# SpeakModule.net
KiCad netlist of a schematic drawn in EAGLE
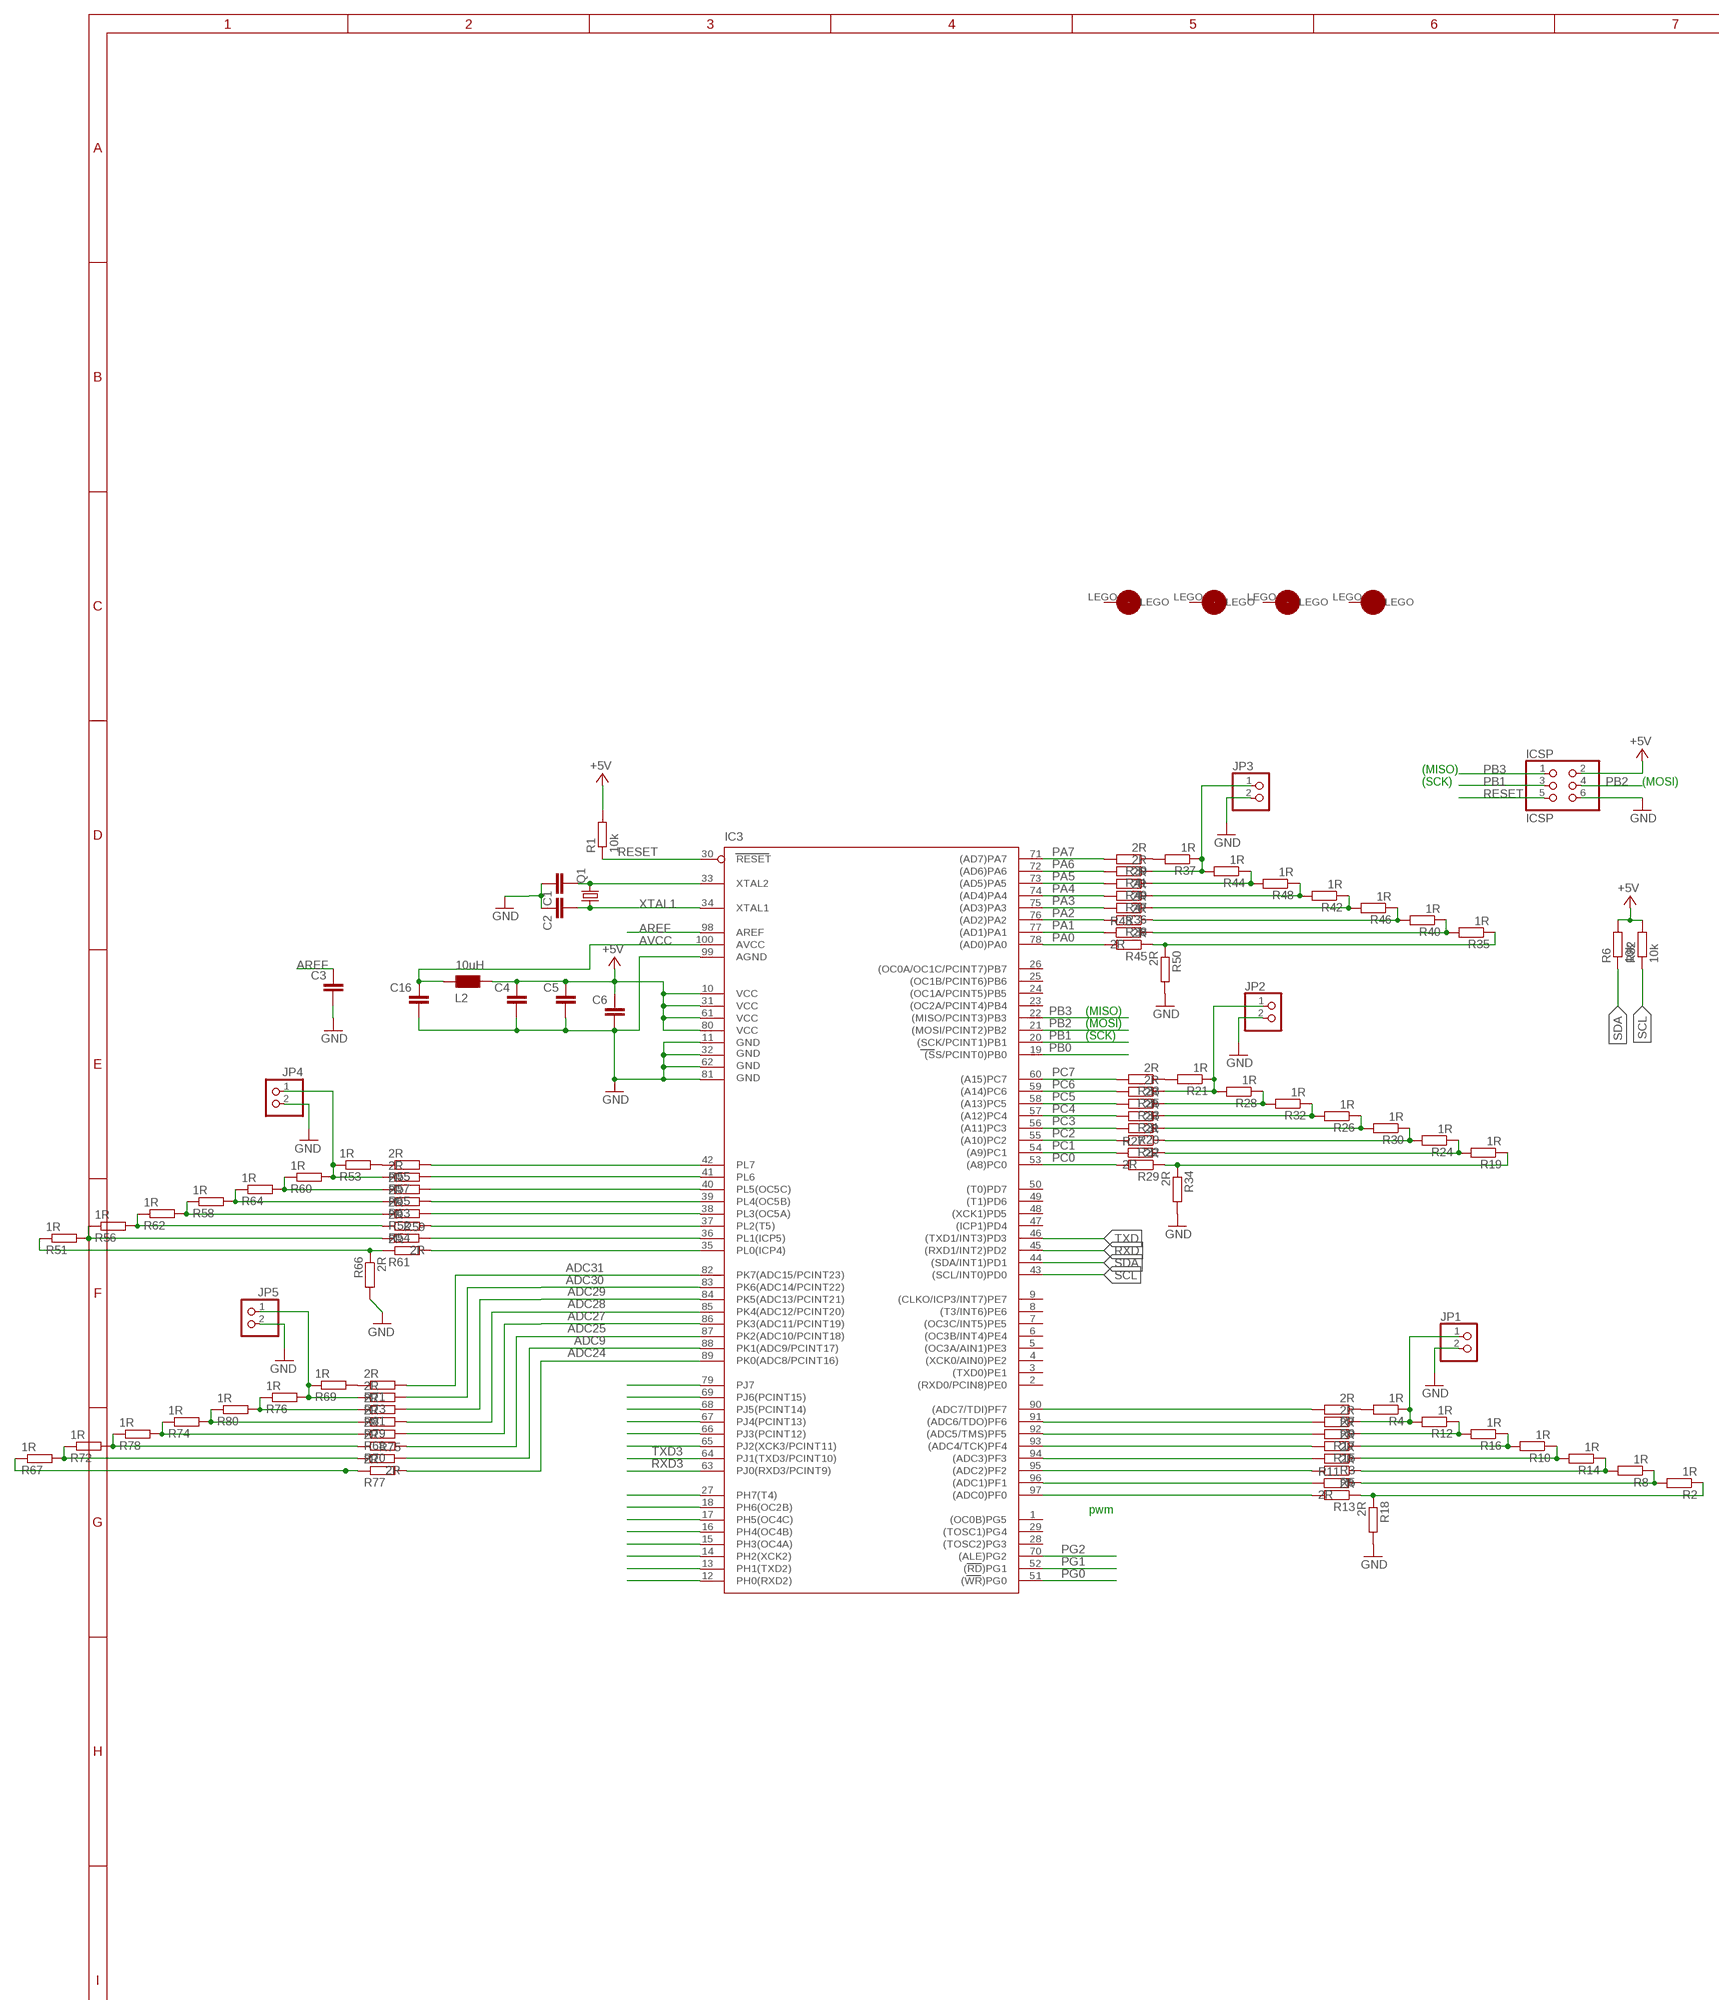
[diagram p0: schematic, sheet 1, part 1 of 2]
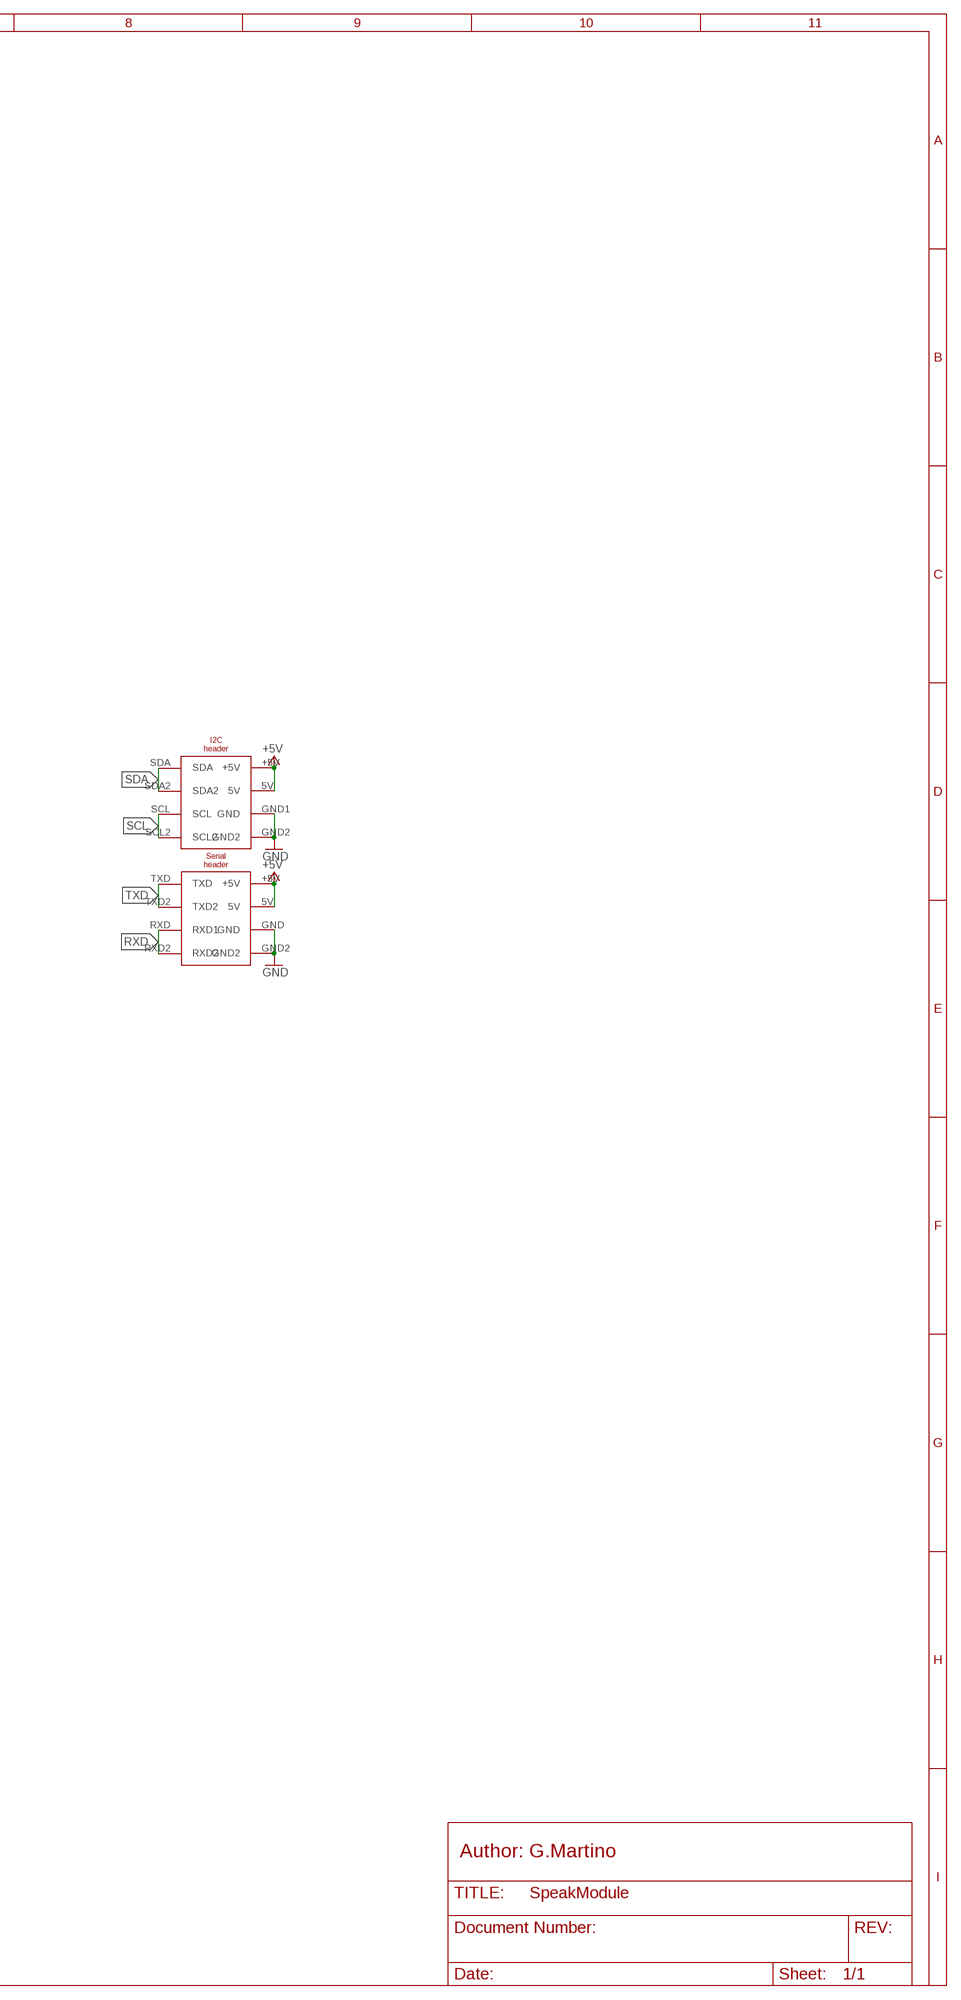
[diagram p1: schematic, sheet 1, part 2 of 2]

(export (version "E")
  (design (tool "Eeschema 10.0.6"))
  (components
    (comp (ref "C1")
      (value "22pf")
      (footprint "eagle-import:C1206")
      (libsource (lib "eagle-import") (part "C-EUC1206"))
    )
    (comp (ref "C2")
      (value "22pf")
      (footprint "eagle-import:C1206")
      (libsource (lib "eagle-import") (part "C-EUC1206"))
    )
    (comp (ref "C3")
      (value "100nF")
      (footprint "eagle-import:C1206")
      (libsource (lib "eagle-import") (part "C-EUC1206"))
    )
    (comp (ref "C4")
      (value "100nF")
      (footprint "eagle-import:C1206")
      (libsource (lib "eagle-import") (part "C-EUC1206"))
    )
    (comp (ref "C5")
      (value "100nF")
      (footprint "eagle-import:C1206")
      (libsource (lib "eagle-import") (part "C-EUC1206"))
    )
    (comp (ref "C6")
      (value "100nF")
      (footprint "eagle-import:C1206")
      (libsource (lib "eagle-import") (part "C-EUC1206"))
    )
    (comp (ref "C16")
      (value "100nF")
      (footprint "eagle-import:C1206")
      (libsource (lib "eagle-import") (part "C-EUC1206"))
    )
    (comp (ref "IC3")
      (value "ATMEGA2560-15AU")
      (footprint "eagle-import:TQFP100")
      (fields (field (name "PART_NUMBER") "ATMEGA2560-16AU"))
      (libsource (lib "eagle-import") (part "0023_ATMEGA2560-16AU"))
    )
    (comp (ref "ICSP")
      (value "ICSP")
      (footprint "eagle-import:2X03")
      (fields (field (name "PART_NUMBER") "PH254-203DF118A00V"))
      (libsource (lib "eagle-import") (part "0114_PH254-203DF118A00V"))
    )
    (comp (ref "JP1")
      (value "PINHD-1X2")
      (footprint "eagle-import:1X02")
      (libsource (lib "eagle-import") (part "PINHD-1X2"))
    )
    (comp (ref "JP2")
      (value "PINHD-1X2")
      (footprint "eagle-import:1X02")
      (libsource (lib "eagle-import") (part "PINHD-1X2"))
    )
    (comp (ref "JP3")
      (value "PINHD-1X2")
      (footprint "eagle-import:1X02")
      (libsource (lib "eagle-import") (part "PINHD-1X2"))
    )
    (comp (ref "JP4")
      (value "PINHD-1X2")
      (footprint "eagle-import:1X02")
      (libsource (lib "eagle-import") (part "PINHD-1X2"))
    )
    (comp (ref "JP5")
      (value "PINHD-1X2")
      (footprint "eagle-import:1X02")
      (libsource (lib "eagle-import") (part "PINHD-1X2"))
    )
    (comp (ref "L2")
      (value "10uH")
      (footprint "eagle-import:0805")
      (fields (field (name "PART_NUMBER") "CV201210-100K"))
      (libsource (lib "eagle-import") (part "0715_CV201210-100K"))
    )
    (comp (ref "Q1")
      (value "CRYSTALHC49S")
      (footprint "eagle-import:HC49_S")
      (libsource (lib "eagle-import") (part "CRYSTALHC49S"))
    )
    (comp (ref "R1")
      (value "10k")
      (footprint "eagle-import:M1206")
      (libsource (lib "eagle-import") (part "R-EU_M1206"))
    )
    (comp (ref "R2")
      (value "1R")
      (footprint "eagle-import:M1206")
      (libsource (lib "eagle-import") (part "R-EU_M1206"))
    )
    (comp (ref "R3")
      (value "2R")
      (footprint "eagle-import:M1206")
      (libsource (lib "eagle-import") (part "R-EU_M1206"))
    )
    (comp (ref "R4")
      (value "1R")
      (footprint "eagle-import:M1206")
      (libsource (lib "eagle-import") (part "R-EU_M1206"))
    )
    (comp (ref "R5")
      (value "2R")
      (footprint "eagle-import:M1206")
      (libsource (lib "eagle-import") (part "R-EU_M1206"))
    )
    (comp (ref "R6")
      (value "10k")
      (footprint "eagle-import:M1206")
      (libsource (lib "eagle-import") (part "R-EU_M1206"))
    )
    (comp (ref "R7")
      (value "2R")
      (footprint "eagle-import:M1206")
      (libsource (lib "eagle-import") (part "R-EU_M1206"))
    )
    (comp (ref "R8")
      (value "1R")
      (footprint "eagle-import:M1206")
      (libsource (lib "eagle-import") (part "R-EU_M1206"))
    )
    (comp (ref "R9")
      (value "2R")
      (footprint "eagle-import:M1206")
      (libsource (lib "eagle-import") (part "R-EU_M1206"))
    )
    (comp (ref "R10")
      (value "1R")
      (footprint "eagle-import:M1206")
      (libsource (lib "eagle-import") (part "R-EU_M1206"))
    )
    (comp (ref "R11")
      (value "2R")
      (footprint "eagle-import:M1206")
      (libsource (lib "eagle-import") (part "R-EU_M1206"))
    )
    (comp (ref "R12")
      (value "1R")
      (footprint "eagle-import:M1206")
      (libsource (lib "eagle-import") (part "R-EU_M1206"))
    )
    (comp (ref "R13")
      (value "2R")
      (footprint "eagle-import:M1206")
      (libsource (lib "eagle-import") (part "R-EU_M1206"))
    )
    (comp (ref "R14")
      (value "1R")
      (footprint "eagle-import:M1206")
      (libsource (lib "eagle-import") (part "R-EU_M1206"))
    )
    (comp (ref "R15")
      (value "2R")
      (footprint "eagle-import:M1206")
      (libsource (lib "eagle-import") (part "R-EU_M1206"))
    )
    (comp (ref "R16")
      (value "1R")
      (footprint "eagle-import:M1206")
      (libsource (lib "eagle-import") (part "R-EU_M1206"))
    )
    (comp (ref "R17")
      (value "2R")
      (footprint "eagle-import:M1206")
      (libsource (lib "eagle-import") (part "R-EU_M1206"))
    )
    (comp (ref "R18")
      (value "2R")
      (footprint "eagle-import:M1206")
      (libsource (lib "eagle-import") (part "R-EU_M1206"))
    )
    (comp (ref "R19")
      (value "1R")
      (footprint "eagle-import:M1206")
      (libsource (lib "eagle-import") (part "R-EU_M1206"))
    )
    (comp (ref "R20")
      (value "2R")
      (footprint "eagle-import:M1206")
      (libsource (lib "eagle-import") (part "R-EU_M1206"))
    )
    (comp (ref "R21")
      (value "1R")
      (footprint "eagle-import:M1206")
      (libsource (lib "eagle-import") (part "R-EU_M1206"))
    )
    (comp (ref "R22")
      (value "2R")
      (footprint "eagle-import:M1206")
      (libsource (lib "eagle-import") (part "R-EU_M1206"))
    )
    (comp (ref "R23")
      (value "2R")
      (footprint "eagle-import:M1206")
      (libsource (lib "eagle-import") (part "R-EU_M1206"))
    )
    (comp (ref "R24")
      (value "1R")
      (footprint "eagle-import:M1206")
      (libsource (lib "eagle-import") (part "R-EU_M1206"))
    )
    (comp (ref "R25")
      (value "2R")
      (footprint "eagle-import:M1206")
      (libsource (lib "eagle-import") (part "R-EU_M1206"))
    )
    (comp (ref "R26")
      (value "1R")
      (footprint "eagle-import:M1206")
      (libsource (lib "eagle-import") (part "R-EU_M1206"))
    )
    (comp (ref "R27")
      (value "2R")
      (footprint "eagle-import:M1206")
      (libsource (lib "eagle-import") (part "R-EU_M1206"))
    )
    (comp (ref "R28")
      (value "1R")
      (footprint "eagle-import:M1206")
      (libsource (lib "eagle-import") (part "R-EU_M1206"))
    )
    (comp (ref "R29")
      (value "2R")
      (footprint "eagle-import:M1206")
      (libsource (lib "eagle-import") (part "R-EU_M1206"))
    )
    (comp (ref "R30")
      (value "1R")
      (footprint "eagle-import:M1206")
      (libsource (lib "eagle-import") (part "R-EU_M1206"))
    )
    (comp (ref "R31")
      (value "2R")
      (footprint "eagle-import:M1206")
      (libsource (lib "eagle-import") (part "R-EU_M1206"))
    )
    (comp (ref "R32")
      (value "1R")
      (footprint "eagle-import:M1206")
      (libsource (lib "eagle-import") (part "R-EU_M1206"))
    )
    (comp (ref "R33")
      (value "2R")
      (footprint "eagle-import:M1206")
      (libsource (lib "eagle-import") (part "R-EU_M1206"))
    )
    (comp (ref "R34")
      (value "2R")
      (footprint "eagle-import:M1206")
      (libsource (lib "eagle-import") (part "R-EU_M1206"))
    )
    (comp (ref "R35")
      (value "1R")
      (footprint "eagle-import:M1206")
      (libsource (lib "eagle-import") (part "R-EU_M1206"))
    )
    (comp (ref "R36")
      (value "2R")
      (footprint "eagle-import:M1206")
      (libsource (lib "eagle-import") (part "R-EU_M1206"))
    )
    (comp (ref "R37")
      (value "1R")
      (footprint "eagle-import:M1206")
      (libsource (lib "eagle-import") (part "R-EU_M1206"))
    )
    (comp (ref "R38")
      (value "2R")
      (footprint "eagle-import:M1206")
      (libsource (lib "eagle-import") (part "R-EU_M1206"))
    )
    (comp (ref "R39")
      (value "2R")
      (footprint "eagle-import:M1206")
      (libsource (lib "eagle-import") (part "R-EU_M1206"))
    )
    (comp (ref "R40")
      (value "1R")
      (footprint "eagle-import:M1206")
      (libsource (lib "eagle-import") (part "R-EU_M1206"))
    )
    (comp (ref "R41")
      (value "2R")
      (footprint "eagle-import:M1206")
      (libsource (lib "eagle-import") (part "R-EU_M1206"))
    )
    (comp (ref "R42")
      (value "1R")
      (footprint "eagle-import:M1206")
      (libsource (lib "eagle-import") (part "R-EU_M1206"))
    )
    (comp (ref "R43")
      (value "2R")
      (footprint "eagle-import:M1206")
      (libsource (lib "eagle-import") (part "R-EU_M1206"))
    )
    (comp (ref "R44")
      (value "1R")
      (footprint "eagle-import:M1206")
      (libsource (lib "eagle-import") (part "R-EU_M1206"))
    )
    (comp (ref "R45")
      (value "2R")
      (footprint "eagle-import:M1206")
      (libsource (lib "eagle-import") (part "R-EU_M1206"))
    )
    (comp (ref "R46")
      (value "1R")
      (footprint "eagle-import:M1206")
      (libsource (lib "eagle-import") (part "R-EU_M1206"))
    )
    (comp (ref "R47")
      (value "2R")
      (footprint "eagle-import:M1206")
      (libsource (lib "eagle-import") (part "R-EU_M1206"))
    )
    (comp (ref "R48")
      (value "1R")
      (footprint "eagle-import:M1206")
      (libsource (lib "eagle-import") (part "R-EU_M1206"))
    )
    (comp (ref "R49")
      (value "2R")
      (footprint "eagle-import:M1206")
      (libsource (lib "eagle-import") (part "R-EU_M1206"))
    )
    (comp (ref "R50")
      (value "2R")
      (footprint "eagle-import:M1206")
      (libsource (lib "eagle-import") (part "R-EU_M1206"))
    )
    (comp (ref "R51")
      (value "1R")
      (footprint "eagle-import:M1206")
      (libsource (lib "eagle-import") (part "R-EU_M1206"))
    )
    (comp (ref "R52")
      (value "2R")
      (footprint "eagle-import:M1206")
      (libsource (lib "eagle-import") (part "R-EU_M1206"))
    )
    (comp (ref "R53")
      (value "1R")
      (footprint "eagle-import:M1206")
      (libsource (lib "eagle-import") (part "R-EU_M1206"))
    )
    (comp (ref "R54")
      (value "2R")
      (footprint "eagle-import:M1206")
      (libsource (lib "eagle-import") (part "R-EU_M1206"))
    )
    (comp (ref "R55")
      (value "2R")
      (footprint "eagle-import:M1206")
      (libsource (lib "eagle-import") (part "R-EU_M1206"))
    )
    (comp (ref "R56")
      (value "1R")
      (footprint "eagle-import:M1206")
      (libsource (lib "eagle-import") (part "R-EU_M1206"))
    )
    (comp (ref "R57")
      (value "2R")
      (footprint "eagle-import:M1206")
      (libsource (lib "eagle-import") (part "R-EU_M1206"))
    )
    (comp (ref "R58")
      (value "1R")
      (footprint "eagle-import:M1206")
      (libsource (lib "eagle-import") (part "R-EU_M1206"))
    )
    (comp (ref "R59")
      (value "2R")
      (footprint "eagle-import:M1206")
      (libsource (lib "eagle-import") (part "R-EU_M1206"))
    )
    (comp (ref "R60")
      (value "1R")
      (footprint "eagle-import:M1206")
      (libsource (lib "eagle-import") (part "R-EU_M1206"))
    )
    (comp (ref "R61")
      (value "2R")
      (footprint "eagle-import:M1206")
      (libsource (lib "eagle-import") (part "R-EU_M1206"))
    )
    (comp (ref "R62")
      (value "1R")
      (footprint "eagle-import:M1206")
      (libsource (lib "eagle-import") (part "R-EU_M1206"))
    )
    (comp (ref "R63")
      (value "2R")
      (footprint "eagle-import:M1206")
      (libsource (lib "eagle-import") (part "R-EU_M1206"))
    )
    (comp (ref "R64")
      (value "1R")
      (footprint "eagle-import:M1206")
      (libsource (lib "eagle-import") (part "R-EU_M1206"))
    )
    (comp (ref "R65")
      (value "2R")
      (footprint "eagle-import:M1206")
      (libsource (lib "eagle-import") (part "R-EU_M1206"))
    )
    (comp (ref "R66")
      (value "2R")
      (footprint "eagle-import:M1206")
      (libsource (lib "eagle-import") (part "R-EU_M1206"))
    )
    (comp (ref "R67")
      (value "1R")
      (footprint "eagle-import:M1206")
      (libsource (lib "eagle-import") (part "R-EU_M1206"))
    )
    (comp (ref "R68")
      (value "2R")
      (footprint "eagle-import:M1206")
      (libsource (lib "eagle-import") (part "R-EU_M1206"))
    )
    (comp (ref "R69")
      (value "1R")
      (footprint "eagle-import:M1206")
      (libsource (lib "eagle-import") (part "R-EU_M1206"))
    )
    (comp (ref "R70")
      (value "2R")
      (footprint "eagle-import:M1206")
      (libsource (lib "eagle-import") (part "R-EU_M1206"))
    )
    (comp (ref "R71")
      (value "2R")
      (footprint "eagle-import:M1206")
      (libsource (lib "eagle-import") (part "R-EU_M1206"))
    )
    (comp (ref "R72")
      (value "1R")
      (footprint "eagle-import:M1206")
      (libsource (lib "eagle-import") (part "R-EU_M1206"))
    )
    (comp (ref "R73")
      (value "2R")
      (footprint "eagle-import:M1206")
      (libsource (lib "eagle-import") (part "R-EU_M1206"))
    )
    (comp (ref "R74")
      (value "1R")
      (footprint "eagle-import:M1206")
      (libsource (lib "eagle-import") (part "R-EU_M1206"))
    )
    (comp (ref "R75")
      (value "2R")
      (footprint "eagle-import:M1206")
      (libsource (lib "eagle-import") (part "R-EU_M1206"))
    )
    (comp (ref "R76")
      (value "1R")
      (footprint "eagle-import:M1206")
      (libsource (lib "eagle-import") (part "R-EU_M1206"))
    )
    (comp (ref "R77")
      (value "2R")
      (footprint "eagle-import:M1206")
      (libsource (lib "eagle-import") (part "R-EU_M1206"))
    )
    (comp (ref "R78")
      (value "1R")
      (footprint "eagle-import:M1206")
      (libsource (lib "eagle-import") (part "R-EU_M1206"))
    )
    (comp (ref "R79")
      (value "2R")
      (footprint "eagle-import:M1206")
      (libsource (lib "eagle-import") (part "R-EU_M1206"))
    )
    (comp (ref "R80")
      (value "1R")
      (footprint "eagle-import:M1206")
      (libsource (lib "eagle-import") (part "R-EU_M1206"))
    )
    (comp (ref "R81")
      (value "2R")
      (footprint "eagle-import:M1206")
      (libsource (lib "eagle-import") (part "R-EU_M1206"))
    )
    (comp (ref "R82")
      (value "10k")
      (footprint "eagle-import:M1206")
      (libsource (lib "eagle-import") (part "R-EU_M1206"))
    )
    (comp (ref "U$1")
      (value "LEGO-1X1")
      (footprint "eagle-import:LEGO-1X1")
      (libsource (lib "eagle-import") (part "LEGO-1X1"))
    )
    (comp (ref "U$2")
      (value "LEGO-1X1")
      (footprint "eagle-import:LEGO-1X1")
      (libsource (lib "eagle-import") (part "LEGO-1X1"))
    )
    (comp (ref "U$3")
      (value "LEGO-1X1")
      (footprint "eagle-import:LEGO-1X1")
      (libsource (lib "eagle-import") (part "LEGO-1X1"))
    )
    (comp (ref "U$4")
      (value "LEGO-1X1")
      (footprint "eagle-import:LEGO-1X1")
      (libsource (lib "eagle-import") (part "LEGO-1X1"))
    )
    (comp (ref "U$5")
      (value "I2C_HEADER")
      (footprint "eagle-import:I2_HEADER")
      (libsource (lib "eagle-import") (part "I2C_HEADER"))
    )
    (comp (ref "U$6")
      (value "SERIAL_HEADER")
      (footprint "eagle-import:SERIAL_HEADER")
      (libsource (lib "eagle-import") (part "SERIAL_HEADER"))
    )
  )
  (nets
    (net (code "1") (name "+5V") (class "Default")
      (node (ref "C4") (pin "1") (pinfunction "1_1") (pintype "passive"))
      (node (ref "C5") (pin "1") (pinfunction "1_1") (pintype "passive"))
      (node (ref "C6") (pin "1") (pinfunction "1_1") (pintype "passive"))
      (node (ref "IC3") (pin "10") (pinfunction "VCC_10") (pintype "power_in"))
      (node (ref "IC3") (pin "31") (pinfunction "VCC1_31") (pintype "power_in"))
      (node (ref "IC3") (pin "61") (pinfunction "VCC2_61") (pintype "power_in"))
      (node (ref "IC3") (pin "80") (pinfunction "VCC3_80") (pintype "power_in"))
      (node (ref "ICSP") (pin "2") (pinfunction "2_2") (pintype "passive"))
      (node (ref "L2") (pin "2") (pinfunction "2_2") (pintype "passive"))
      (node (ref "R1") (pin "2") (pinfunction "2_2") (pintype "passive"))
      (node (ref "R6") (pin "2") (pinfunction "2_2") (pintype "passive"))
      (node (ref "R82") (pin "2") (pinfunction "2_2") (pintype "passive"))
      (node (ref "U$5") (pin "+5V") (pinfunction "+5V_+5V") (pintype "bidirectional"))
      (node (ref "U$5") (pin "5V") (pinfunction "5V_5V") (pintype "bidirectional"))
      (node (ref "U$6") (pin "+5V") (pinfunction "+5V_+5V") (pintype "bidirectional"))
      (node (ref "U$6") (pin "5V") (pinfunction "5V_5V") (pintype "bidirectional"))
    )
    (net (code "2") (name "/ADC9") (class "Default")
      (node (ref "IC3") (pin "88") (pinfunction "PK1(ADC9/PCINT17)_88") (pintype "bidirectional"))
      (node (ref "R75") (pin "1") (pinfunction "1_1") (pintype "passive"))
    )
    (net (code "3") (name "/ADC24") (class "Default")
      (node (ref "IC3") (pin "89") (pinfunction "PK0(ADC8/PCINT16)_89") (pintype "bidirectional"))
      (node (ref "R77") (pin "2") (pinfunction "2_2") (pintype "passive"))
    )
    (net (code "4") (name "/ADC25") (class "Default")
      (node (ref "IC3") (pin "87") (pinfunction "PK2(ADC10/PCINT18)_87") (pintype "bidirectional"))
      (node (ref "R70") (pin "2") (pinfunction "2_2") (pintype "passive"))
    )
    (net (code "5") (name "/ADC27") (class "Default")
      (node (ref "IC3") (pin "86") (pinfunction "PK3(ADC11/PCINT19)_86") (pintype "bidirectional"))
      (node (ref "R68") (pin "2") (pinfunction "2_2") (pintype "passive"))
    )
    (net (code "6") (name "/ADC28") (class "Default")
      (node (ref "IC3") (pin "85") (pinfunction "PK4(ADC12/PCINT20)_85") (pintype "bidirectional"))
      (node (ref "R79") (pin "2") (pinfunction "2_2") (pintype "passive"))
    )
    (net (code "7") (name "/ADC29") (class "Default")
      (node (ref "IC3") (pin "84") (pinfunction "PK5(ADC13/PCINT21)_84") (pintype "bidirectional"))
      (node (ref "R81") (pin "2") (pinfunction "2_2") (pintype "passive"))
    )
    (net (code "8") (name "/ADC30") (class "Default")
      (node (ref "IC3") (pin "83") (pinfunction "PK6(ADC14/PCINT22)_83") (pintype "bidirectional"))
      (node (ref "R73") (pin "2") (pinfunction "2_2") (pintype "passive"))
    )
    (net (code "9") (name "/ADC31") (class "Default")
      (node (ref "IC3") (pin "82") (pinfunction "PK7(ADC15/PCINT23)_82") (pintype "bidirectional"))
      (node (ref "R71") (pin "2") (pinfunction "2_2") (pintype "passive"))
    )
    (net (code "10") (name "/AREF") (class "Default")
      (node (ref "C3") (pin "1") (pinfunction "1_1") (pintype "passive"))
      (node (ref "IC3") (pin "98") (pinfunction "AREF_98") (pintype "bidirectional"))
    )
    (net (code "11") (name "/AVCC") (class "Default")
      (node (ref "C16") (pin "1") (pinfunction "1_1") (pintype "passive"))
      (node (ref "IC3") (pin "100") (pinfunction "AVCC_100") (pintype "power_in"))
      (node (ref "L2") (pin "1") (pinfunction "1_1") (pintype "passive"))
    )
    (net (code "12") (name "/PA0") (class "Default")
      (node (ref "IC3") (pin "78") (pinfunction "(AD0)PA0_78") (pintype "bidirectional"))
      (node (ref "R45") (pin "2") (pinfunction "2_2") (pintype "passive"))
    )
    (net (code "13") (name "/PA1") (class "Default")
      (node (ref "IC3") (pin "77") (pinfunction "(AD1)PA1_77") (pintype "bidirectional"))
      (node (ref "R43") (pin "1") (pinfunction "1_1") (pintype "passive"))
    )
    (net (code "14") (name "/PA2") (class "Default")
      (node (ref "IC3") (pin "76") (pinfunction "(AD2)PA2_76") (pintype "bidirectional"))
      (node (ref "R38") (pin "2") (pinfunction "2_2") (pintype "passive"))
    )
    (net (code "15") (name "/PA3") (class "Default")
      (node (ref "IC3") (pin "75") (pinfunction "(AD3)PA3_75") (pintype "bidirectional"))
      (node (ref "R36") (pin "2") (pinfunction "2_2") (pintype "passive"))
    )
    (net (code "16") (name "/PA4") (class "Default")
      (node (ref "IC3") (pin "74") (pinfunction "(AD4)PA4_74") (pintype "bidirectional"))
      (node (ref "R47") (pin "2") (pinfunction "2_2") (pintype "passive"))
    )
    (net (code "17") (name "/PA5") (class "Default")
      (node (ref "IC3") (pin "73") (pinfunction "(AD5)PA5_73") (pintype "bidirectional"))
      (node (ref "R49") (pin "2") (pinfunction "2_2") (pintype "passive"))
    )
    (net (code "18") (name "/PA6") (class "Default")
      (node (ref "IC3") (pin "72") (pinfunction "(AD6)PA6_72") (pintype "bidirectional"))
      (node (ref "R41") (pin "2") (pinfunction "2_2") (pintype "passive"))
    )
    (net (code "19") (name "/PA7") (class "Default")
      (node (ref "IC3") (pin "71") (pinfunction "(AD7)PA7_71") (pintype "bidirectional"))
      (node (ref "R39") (pin "2") (pinfunction "2_2") (pintype "passive"))
    )
    (net (code "20") (name "/PB0") (class "Default")
      (node (ref "IC3") (pin "19") (pinfunction "(SS/PCINT0)PB0_19") (pintype "bidirectional"))
    )
    (net (code "21") (name "/PB1") (class "Default")
      (node (ref "IC3") (pin "20") (pinfunction "(SCK/PCINT1)PB1_20") (pintype "bidirectional"))
      (node (ref "ICSP") (pin "3") (pinfunction "3_3") (pintype "passive"))
    )
    (net (code "22") (name "/PB2") (class "Default")
      (node (ref "IC3") (pin "21") (pinfunction "(MOSI/PCINT2)PB2_21") (pintype "bidirectional"))
      (node (ref "ICSP") (pin "4") (pinfunction "4_4") (pintype "passive"))
    )
    (net (code "23") (name "/PB3") (class "Default")
      (node (ref "IC3") (pin "22") (pinfunction "(MISO/PCINT3)PB3_22") (pintype "bidirectional"))
      (node (ref "ICSP") (pin "1") (pinfunction "1_1") (pintype "passive"))
    )
    (net (code "24") (name "/PC0") (class "Default")
      (node (ref "IC3") (pin "53") (pinfunction "(A8)PC0_53") (pintype "bidirectional"))
      (node (ref "R29") (pin "2") (pinfunction "2_2") (pintype "passive"))
    )
    (net (code "25") (name "/PC1") (class "Default")
      (node (ref "IC3") (pin "54") (pinfunction "(A9)PC1_54") (pintype "bidirectional"))
      (node (ref "R27") (pin "1") (pinfunction "1_1") (pintype "passive"))
    )
    (net (code "26") (name "/PC2") (class "Default")
      (node (ref "IC3") (pin "55") (pinfunction "(A10)PC2_55") (pintype "bidirectional"))
      (node (ref "R22") (pin "2") (pinfunction "2_2") (pintype "passive"))
    )
    (net (code "27") (name "/PC3") (class "Default")
      (node (ref "IC3") (pin "56") (pinfunction "(A11)PC3_56") (pintype "bidirectional"))
      (node (ref "R20") (pin "2") (pinfunction "2_2") (pintype "passive"))
    )
    (net (code "28") (name "/PC4") (class "Default")
      (node (ref "IC3") (pin "57") (pinfunction "(A12)PC4_57") (pintype "bidirectional"))
      (node (ref "R31") (pin "2") (pinfunction "2_2") (pintype "passive"))
    )
    (net (code "29") (name "/PC5") (class "Default")
      (node (ref "IC3") (pin "58") (pinfunction "(A13)PC5_58") (pintype "bidirectional"))
      (node (ref "R33") (pin "2") (pinfunction "2_2") (pintype "passive"))
    )
    (net (code "30") (name "/PC6") (class "Default")
      (node (ref "IC3") (pin "59") (pinfunction "(A14)PC6_59") (pintype "bidirectional"))
      (node (ref "R25") (pin "2") (pinfunction "2_2") (pintype "passive"))
    )
    (net (code "31") (name "/PC7") (class "Default")
      (node (ref "IC3") (pin "60") (pinfunction "(A15)PC7_60") (pintype "bidirectional"))
      (node (ref "R23") (pin "2") (pinfunction "2_2") (pintype "passive"))
    )
    (net (code "32") (name "/PG0") (class "Default")
      (node (ref "IC3") (pin "51") (pinfunction "(WR)PG0_51") (pintype "bidirectional"))
    )
    (net (code "33") (name "/PG1") (class "Default")
      (node (ref "IC3") (pin "52") (pinfunction "(RD)PG1_52") (pintype "bidirectional"))
    )
    (net (code "34") (name "/PG2") (class "Default")
      (node (ref "IC3") (pin "70") (pinfunction "(ALE)PG2_70") (pintype "bidirectional"))
    )
    (net (code "35") (name "/RESET") (class "Default")
      (node (ref "IC3") (pin "30") (pinfunction "RESET_30") (pintype "input"))
      (node (ref "ICSP") (pin "5") (pinfunction "5_5") (pintype "passive"))
      (node (ref "R1") (pin "1") (pinfunction "1_1") (pintype "passive"))
    )
    (net (code "36") (name "/RXD3") (class "Default")
      (node (ref "IC3") (pin "63") (pinfunction "PJ0(RXD3/PCINT9)_63") (pintype "bidirectional"))
    )
    (net (code "37") (name "/TXD3") (class "Default")
      (node (ref "IC3") (pin "64") (pinfunction "PJ1(TXD3/PCINT10)_64") (pintype "bidirectional"))
    )
    (net (code "38") (name "/XTAL1") (class "Default")
      (node (ref "C2") (pin "2") (pinfunction "2_2") (pintype "passive"))
      (node (ref "IC3") (pin "34") (pinfunction "XTAL1_34") (pintype "input"))
      (node (ref "Q1") (pin "1") (pinfunction "1_1") (pintype "passive"))
    )
    (net (code "39") (name "GND") (class "Default")
      (node (ref "C1") (pin "1") (pinfunction "1_1") (pintype "passive"))
      (node (ref "C16") (pin "2") (pinfunction "2_2") (pintype "passive"))
      (node (ref "C2") (pin "1") (pinfunction "1_1") (pintype "passive"))
      (node (ref "C3") (pin "2") (pinfunction "2_2") (pintype "passive"))
      (node (ref "C4") (pin "2") (pinfunction "2_2") (pintype "passive"))
      (node (ref "C5") (pin "2") (pinfunction "2_2") (pintype "passive"))
      (node (ref "C6") (pin "2") (pinfunction "2_2") (pintype "passive"))
      (node (ref "IC3") (pin "11") (pinfunction "GND_11") (pintype "power_in"))
      (node (ref "IC3") (pin "32") (pinfunction "GND1_32") (pintype "power_in"))
      (node (ref "IC3") (pin "62") (pinfunction "GND2_62") (pintype "power_in"))
      (node (ref "IC3") (pin "81") (pinfunction "GND3_81") (pintype "power_in"))
      (node (ref "IC3") (pin "99") (pinfunction "AGND_99") (pintype "power_in"))
      (node (ref "ICSP") (pin "6") (pinfunction "6_6") (pintype "passive"))
      (node (ref "JP1") (pin "2") (pinfunction "2_2") (pintype "passive"))
      (node (ref "JP2") (pin "2") (pinfunction "2_2") (pintype "passive"))
      (node (ref "JP3") (pin "2") (pinfunction "2_2") (pintype "passive"))
      (node (ref "JP4") (pin "2") (pinfunction "2_2") (pintype "passive"))
      (node (ref "JP5") (pin "2") (pinfunction "2_2") (pintype "passive"))
      (node (ref "R18") (pin "2") (pinfunction "2_2") (pintype "passive"))
      (node (ref "R34") (pin "2") (pinfunction "2_2") (pintype "passive"))
      (node (ref "R50") (pin "2") (pinfunction "2_2") (pintype "passive"))
      (node (ref "R66") (pin "2") (pinfunction "2_2") (pintype "passive"))
      (node (ref "U$5") (pin "GND1") (pinfunction "GND_GND1") (pintype "bidirectional"))
      (node (ref "U$5") (pin "GND2") (pinfunction "GND2_GND2") (pintype "bidirectional"))
      (node (ref "U$6") (pin "GND") (pinfunction "GND_GND") (pintype "bidirectional"))
      (node (ref "U$6") (pin "GND2") (pinfunction "GND2_GND2") (pintype "bidirectional"))
    )
    (net (code "40") (name "Net-(IC3-(ADC0)PF0)") (class "Default")
      (node (ref "IC3") (pin "97") (pinfunction "(ADC0)PF0_97") (pintype "bidirectional"))
      (node (ref "R13") (pin "2") (pinfunction "2_2") (pintype "passive"))
    )
    (net (code "41") (name "Net-(IC3-(ADC1)PF1)") (class "Default")
      (node (ref "IC3") (pin "96") (pinfunction "(ADC1)PF1_96") (pintype "bidirectional"))
      (node (ref "R11") (pin "1") (pinfunction "1_1") (pintype "passive"))
    )
    (net (code "42") (name "Net-(IC3-(ADC2)PF2)") (class "Default")
      (node (ref "IC3") (pin "95") (pinfunction "(ADC2)PF2_95") (pintype "bidirectional"))
      (node (ref "R5") (pin "2") (pinfunction "2_2") (pintype "passive"))
    )
    (net (code "43") (name "Net-(IC3-(ADC3)PF3)") (class "Default")
      (node (ref "IC3") (pin "94") (pinfunction "(ADC3)PF3_94") (pintype "bidirectional"))
      (node (ref "R3") (pin "2") (pinfunction "2_2") (pintype "passive"))
    )
    (net (code "44") (name "Net-(IC3-(ADC4{slash}TCK)PF4)") (class "Default")
      (node (ref "IC3") (pin "93") (pinfunction "(ADC4/TCK)PF4_93") (pintype "bidirectional"))
      (node (ref "R15") (pin "2") (pinfunction "2_2") (pintype "passive"))
    )
    (net (code "45") (name "Net-(IC3-(ADC5{slash}TMS)PF5)") (class "Default")
      (node (ref "IC3") (pin "92") (pinfunction "(ADC5/TMS)PF5_92") (pintype "bidirectional"))
      (node (ref "R17") (pin "2") (pinfunction "2_2") (pintype "passive"))
    )
    (net (code "46") (name "Net-(IC3-(ADC6{slash}TDO)PF6)") (class "Default")
      (node (ref "IC3") (pin "91") (pinfunction "(ADC6/TDO)PF6_91") (pintype "bidirectional"))
      (node (ref "R9") (pin "2") (pinfunction "2_2") (pintype "passive"))
    )
    (net (code "47") (name "Net-(IC3-(ADC7{slash}TDI)PF7)") (class "Default")
      (node (ref "IC3") (pin "90") (pinfunction "(ADC7/TDI)PF7_90") (pintype "bidirectional"))
      (node (ref "R7") (pin "2") (pinfunction "2_2") (pintype "passive"))
    )
    (net (code "48") (name "Net-(IC3-PL0(ICP4))") (class "Default")
      (node (ref "IC3") (pin "35") (pinfunction "PL0(ICP4)_35") (pintype "bidirectional"))
      (node (ref "R61") (pin "2") (pinfunction "2_2") (pintype "passive"))
    )
    (net (code "49") (name "Net-(IC3-PL1(ICP5))") (class "Default")
      (node (ref "IC3") (pin "36") (pinfunction "PL1(ICP5)_36") (pintype "bidirectional"))
      (node (ref "R59") (pin "1") (pinfunction "1_1") (pintype "passive"))
    )
    (net (code "50") (name "Net-(IC3-PL2(T5))") (class "Default")
      (node (ref "IC3") (pin "37") (pinfunction "PL2(T5)_37") (pintype "bidirectional"))
      (node (ref "R54") (pin "2") (pinfunction "2_2") (pintype "passive"))
    )
    (net (code "51") (name "Net-(IC3-PL3(OC5A))") (class "Default")
      (node (ref "IC3") (pin "38") (pinfunction "PL3(OC5A)_38") (pintype "bidirectional"))
      (node (ref "R52") (pin "2") (pinfunction "2_2") (pintype "passive"))
    )
    (net (code "52") (name "Net-(IC3-PL4(OC5B))") (class "Default")
      (node (ref "IC3") (pin "39") (pinfunction "PL4(OC5B)_39") (pintype "bidirectional"))
      (node (ref "R63") (pin "2") (pinfunction "2_2") (pintype "passive"))
    )
    (net (code "53") (name "Net-(IC3-PL5(OC5C))") (class "Default")
      (node (ref "IC3") (pin "40") (pinfunction "PL5(OC5C)_40") (pintype "bidirectional"))
      (node (ref "R65") (pin "2") (pinfunction "2_2") (pintype "passive"))
    )
    (net (code "54") (name "Net-(IC3-PL6)") (class "Default")
      (node (ref "IC3") (pin "41") (pinfunction "PL6_41") (pintype "bidirectional"))
      (node (ref "R57") (pin "2") (pinfunction "2_2") (pintype "passive"))
    )
    (net (code "55") (name "Net-(IC3-PL7)") (class "Default")
      (node (ref "IC3") (pin "42") (pinfunction "PL7_42") (pintype "bidirectional"))
      (node (ref "R55") (pin "2") (pinfunction "2_2") (pintype "passive"))
    )
    (net (code "56") (name "Net-(IC3-XTAL2)") (class "Default")
      (node (ref "C1") (pin "2") (pinfunction "2_2") (pintype "passive"))
      (node (ref "IC3") (pin "33") (pinfunction "XTAL2_33") (pintype "output"))
      (node (ref "Q1") (pin "2") (pinfunction "2_2") (pintype "passive"))
    )
    (net (code "57") (name "Net-(JP1-Pad1)") (class "Default")
      (node (ref "JP1") (pin "1") (pinfunction "1_1") (pintype "passive"))
      (node (ref "R12") (pin "2") (pinfunction "2_2") (pintype "passive"))
      (node (ref "R4") (pin "1") (pinfunction "1_1") (pintype "passive"))
      (node (ref "R9") (pin "1") (pinfunction "1_1") (pintype "passive"))
    )
    (net (code "58") (name "Net-(JP2-Pad1)") (class "Default")
      (node (ref "JP2") (pin "1") (pinfunction "1_1") (pintype "passive"))
      (node (ref "R21") (pin "1") (pinfunction "1_1") (pintype "passive"))
      (node (ref "R25") (pin "1") (pinfunction "1_1") (pintype "passive"))
      (node (ref "R28") (pin "2") (pinfunction "2_2") (pintype "passive"))
    )
    (net (code "59") (name "Net-(JP3-Pad1)") (class "Default")
      (node (ref "JP3") (pin "1") (pinfunction "1_1") (pintype "passive"))
      (node (ref "R37") (pin "1") (pinfunction "1_1") (pintype "passive"))
      (node (ref "R41") (pin "1") (pinfunction "1_1") (pintype "passive"))
      (node (ref "R44") (pin "2") (pinfunction "2_2") (pintype "passive"))
    )
    (net (code "60") (name "Net-(JP4-Pad1)") (class "Default")
      (node (ref "JP4") (pin "1") (pinfunction "1_1") (pintype "passive"))
      (node (ref "R53") (pin "1") (pinfunction "1_1") (pintype "passive"))
      (node (ref "R57") (pin "1") (pinfunction "1_1") (pintype "passive"))
      (node (ref "R60") (pin "2") (pinfunction "2_2") (pintype "passive"))
    )
    (net (code "61") (name "Net-(JP5-Pad1)") (class "Default")
      (node (ref "JP5") (pin "1") (pinfunction "1_1") (pintype "passive"))
      (node (ref "R69") (pin "1") (pinfunction "1_1") (pintype "passive"))
      (node (ref "R73") (pin "1") (pinfunction "1_1") (pintype "passive"))
      (node (ref "R76") (pin "2") (pinfunction "2_2") (pintype "passive"))
    )
    (net (code "62") (name "Net-(R4-Pad2)") (class "Default")
      (node (ref "R4") (pin "2") (pinfunction "2_2") (pintype "passive"))
      (node (ref "R7") (pin "1") (pinfunction "1_1") (pintype "passive"))
    )
    (net (code "63") (name "Net-(R10-Pad1)") (class "Default")
      (node (ref "R10") (pin "1") (pinfunction "1_1") (pintype "passive"))
      (node (ref "R14") (pin "2") (pinfunction "2_2") (pintype "passive"))
      (node (ref "R3") (pin "1") (pinfunction "1_1") (pintype "passive"))
    )
    (net (code "64") (name "Net-(R10-Pad2)") (class "Default")
      (node (ref "R10") (pin "2") (pinfunction "2_2") (pintype "passive"))
      (node (ref "R15") (pin "1") (pinfunction "1_1") (pintype "passive"))
      (node (ref "R16") (pin "1") (pinfunction "1_1") (pintype "passive"))
    )
    (net (code "65") (name "Net-(R11-Pad2)") (class "Default")
      (node (ref "R11") (pin "2") (pinfunction "2_2") (pintype "passive"))
      (node (ref "R2") (pin "2") (pinfunction "2_2") (pintype "passive"))
      (node (ref "R8") (pin "1") (pinfunction "1_1") (pintype "passive"))
    )
    (net (code "66") (name "Net-(R12-Pad1)") (class "Default")
      (node (ref "R12") (pin "1") (pinfunction "1_1") (pintype "passive"))
      (node (ref "R16") (pin "2") (pinfunction "2_2") (pintype "passive"))
      (node (ref "R17") (pin "1") (pinfunction "1_1") (pintype "passive"))
    )
    (net (code "67") (name "Net-(R13-Pad1)") (class "Default")
      (node (ref "R13") (pin "1") (pinfunction "1_1") (pintype "passive"))
      (node (ref "R18") (pin "1") (pinfunction "1_1") (pintype "passive"))
      (node (ref "R2") (pin "1") (pinfunction "1_1") (pintype "passive"))
    )
    (net (code "68") (name "Net-(R14-Pad1)") (class "Default")
      (node (ref "R14") (pin "1") (pinfunction "1_1") (pintype "passive"))
      (node (ref "R5") (pin "1") (pinfunction "1_1") (pintype "passive"))
      (node (ref "R8") (pin "2") (pinfunction "2_2") (pintype "passive"))
    )
    (net (code "69") (name "Net-(R19-Pad1)") (class "Default")
      (node (ref "R19") (pin "1") (pinfunction "1_1") (pintype "passive"))
      (node (ref "R29") (pin "1") (pinfunction "1_1") (pintype "passive"))
      (node (ref "R34") (pin "1") (pinfunction "1_1") (pintype "passive"))
    )
    (net (code "70") (name "Net-(R19-Pad2)") (class "Default")
      (node (ref "R19") (pin "2") (pinfunction "2_2") (pintype "passive"))
      (node (ref "R24") (pin "1") (pinfunction "1_1") (pintype "passive"))
      (node (ref "R27") (pin "2") (pinfunction "2_2") (pintype "passive"))
    )
    (net (code "71") (name "Net-(R20-Pad1)") (class "Default")
      (node (ref "R20") (pin "1") (pinfunction "1_1") (pintype "passive"))
      (node (ref "R26") (pin "1") (pinfunction "1_1") (pintype "passive"))
      (node (ref "R30") (pin "2") (pinfunction "2_2") (pintype "passive"))
    )
    (net (code "72") (name "Net-(R21-Pad2)") (class "Default")
      (node (ref "R21") (pin "2") (pinfunction "2_2") (pintype "passive"))
      (node (ref "R23") (pin "1") (pinfunction "1_1") (pintype "passive"))
    )
    (net (code "73") (name "Net-(R22-Pad1)") (class "Default")
      (node (ref "R22") (pin "1") (pinfunction "1_1") (pintype "passive"))
      (node (ref "R24") (pin "2") (pinfunction "2_2") (pintype "passive"))
      (node (ref "R30") (pin "1") (pinfunction "1_1") (pintype "passive"))
    )
    (net (code "74") (name "Net-(R26-Pad2)") (class "Default")
      (node (ref "R26") (pin "2") (pinfunction "2_2") (pintype "passive"))
      (node (ref "R31") (pin "1") (pinfunction "1_1") (pintype "passive"))
      (node (ref "R32") (pin "1") (pinfunction "1_1") (pintype "passive"))
    )
    (net (code "75") (name "Net-(R28-Pad1)") (class "Default")
      (node (ref "R28") (pin "1") (pinfunction "1_1") (pintype "passive"))
      (node (ref "R32") (pin "2") (pinfunction "2_2") (pintype "passive"))
      (node (ref "R33") (pin "1") (pinfunction "1_1") (pintype "passive"))
    )
    (net (code "76") (name "Net-(R35-Pad1)") (class "Default")
      (node (ref "R35") (pin "1") (pinfunction "1_1") (pintype "passive"))
      (node (ref "R45") (pin "1") (pinfunction "1_1") (pintype "passive"))
      (node (ref "R50") (pin "1") (pinfunction "1_1") (pintype "passive"))
    )
    (net (code "77") (name "Net-(R35-Pad2)") (class "Default")
      (node (ref "R35") (pin "2") (pinfunction "2_2") (pintype "passive"))
      (node (ref "R40") (pin "1") (pinfunction "1_1") (pintype "passive"))
      (node (ref "R43") (pin "2") (pinfunction "2_2") (pintype "passive"))
    )
    (net (code "78") (name "Net-(R36-Pad1)") (class "Default")
      (node (ref "R36") (pin "1") (pinfunction "1_1") (pintype "passive"))
      (node (ref "R42") (pin "1") (pinfunction "1_1") (pintype "passive"))
      (node (ref "R46") (pin "2") (pinfunction "2_2") (pintype "passive"))
    )
    (net (code "79") (name "Net-(R37-Pad2)") (class "Default")
      (node (ref "R37") (pin "2") (pinfunction "2_2") (pintype "passive"))
      (node (ref "R39") (pin "1") (pinfunction "1_1") (pintype "passive"))
    )
    (net (code "80") (name "Net-(R38-Pad1)") (class "Default")
      (node (ref "R38") (pin "1") (pinfunction "1_1") (pintype "passive"))
      (node (ref "R40") (pin "2") (pinfunction "2_2") (pintype "passive"))
      (node (ref "R46") (pin "1") (pinfunction "1_1") (pintype "passive"))
    )
    (net (code "81") (name "Net-(R42-Pad2)") (class "Default")
      (node (ref "R42") (pin "2") (pinfunction "2_2") (pintype "passive"))
      (node (ref "R47") (pin "1") (pinfunction "1_1") (pintype "passive"))
      (node (ref "R48") (pin "1") (pinfunction "1_1") (pintype "passive"))
    )
    (net (code "82") (name "Net-(R44-Pad1)") (class "Default")
      (node (ref "R44") (pin "1") (pinfunction "1_1") (pintype "passive"))
      (node (ref "R48") (pin "2") (pinfunction "2_2") (pintype "passive"))
      (node (ref "R49") (pin "1") (pinfunction "1_1") (pintype "passive"))
    )
    (net (code "83") (name "Net-(R51-Pad1)") (class "Default")
      (node (ref "R51") (pin "1") (pinfunction "1_1") (pintype "passive"))
      (node (ref "R61") (pin "1") (pinfunction "1_1") (pintype "passive"))
      (node (ref "R66") (pin "1") (pinfunction "1_1") (pintype "passive"))
    )
    (net (code "84") (name "Net-(R51-Pad2)") (class "Default")
      (node (ref "R51") (pin "2") (pinfunction "2_2") (pintype "passive"))
      (node (ref "R56") (pin "1") (pinfunction "1_1") (pintype "passive"))
      (node (ref "R59") (pin "2") (pinfunction "2_2") (pintype "passive"))
    )
    (net (code "85") (name "Net-(R52-Pad1)") (class "Default")
      (node (ref "R52") (pin "1") (pinfunction "1_1") (pintype "passive"))
      (node (ref "R58") (pin "1") (pinfunction "1_1") (pintype "passive"))
      (node (ref "R62") (pin "2") (pinfunction "2_2") (pintype "passive"))
    )
    (net (code "86") (name "Net-(R53-Pad2)") (class "Default")
      (node (ref "R53") (pin "2") (pinfunction "2_2") (pintype "passive"))
      (node (ref "R55") (pin "1") (pinfunction "1_1") (pintype "passive"))
    )
    (net (code "87") (name "Net-(R54-Pad1)") (class "Default")
      (node (ref "R54") (pin "1") (pinfunction "1_1") (pintype "passive"))
      (node (ref "R56") (pin "2") (pinfunction "2_2") (pintype "passive"))
      (node (ref "R62") (pin "1") (pinfunction "1_1") (pintype "passive"))
    )
    (net (code "88") (name "Net-(R58-Pad2)") (class "Default")
      (node (ref "R58") (pin "2") (pinfunction "2_2") (pintype "passive"))
      (node (ref "R63") (pin "1") (pinfunction "1_1") (pintype "passive"))
      (node (ref "R64") (pin "1") (pinfunction "1_1") (pintype "passive"))
    )
    (net (code "89") (name "Net-(R60-Pad1)") (class "Default")
      (node (ref "R60") (pin "1") (pinfunction "1_1") (pintype "passive"))
      (node (ref "R64") (pin "2") (pinfunction "2_2") (pintype "passive"))
      (node (ref "R65") (pin "1") (pinfunction "1_1") (pintype "passive"))
    )
    (net (code "90") (name "Net-(R67-Pad1)") (class "Default")
      (node (ref "R67") (pin "1") (pinfunction "1_1") (pintype "passive"))
      (node (ref "R77") (pin "1") (pinfunction "1_1") (pintype "passive"))
    )
    (net (code "91") (name "Net-(R67-Pad2)") (class "Default")
      (node (ref "R67") (pin "2") (pinfunction "2_2") (pintype "passive"))
      (node (ref "R72") (pin "1") (pinfunction "1_1") (pintype "passive"))
      (node (ref "R75") (pin "2") (pinfunction "2_2") (pintype "passive"))
    )
    (net (code "92") (name "Net-(R68-Pad1)") (class "Default")
      (node (ref "R68") (pin "1") (pinfunction "1_1") (pintype "passive"))
      (node (ref "R74") (pin "1") (pinfunction "1_1") (pintype "passive"))
      (node (ref "R78") (pin "2") (pinfunction "2_2") (pintype "passive"))
    )
    (net (code "93") (name "Net-(R69-Pad2)") (class "Default")
      (node (ref "R69") (pin "2") (pinfunction "2_2") (pintype "passive"))
      (node (ref "R71") (pin "1") (pinfunction "1_1") (pintype "passive"))
    )
    (net (code "94") (name "Net-(R70-Pad1)") (class "Default")
      (node (ref "R70") (pin "1") (pinfunction "1_1") (pintype "passive"))
      (node (ref "R72") (pin "2") (pinfunction "2_2") (pintype "passive"))
      (node (ref "R78") (pin "1") (pinfunction "1_1") (pintype "passive"))
    )
    (net (code "95") (name "Net-(R74-Pad2)") (class "Default")
      (node (ref "R74") (pin "2") (pinfunction "2_2") (pintype "passive"))
      (node (ref "R79") (pin "1") (pinfunction "1_1") (pintype "passive"))
      (node (ref "R80") (pin "1") (pinfunction "1_1") (pintype "passive"))
    )
    (net (code "96") (name "Net-(R76-Pad1)") (class "Default")
      (node (ref "R76") (pin "1") (pinfunction "1_1") (pintype "passive"))
      (node (ref "R80") (pin "2") (pinfunction "2_2") (pintype "passive"))
      (node (ref "R81") (pin "1") (pinfunction "1_1") (pintype "passive"))
    )
    (net (code "97") (name "RXD") (class "Default")
      (node (ref "IC3") (pin "45") (pinfunction "(RXD1/INT2)PD2_45") (pintype "bidirectional"))
      (node (ref "U$6") (pin "RXD") (pinfunction "RXD1_RXD") (pintype "bidirectional"))
      (node (ref "U$6") (pin "RXD2") (pinfunction "RXD2_RXD2") (pintype "bidirectional"))
    )
    (net (code "98") (name "SCL") (class "Default")
      (node (ref "IC3") (pin "43") (pinfunction "(SCL/INT0)PD0_43") (pintype "bidirectional"))
      (node (ref "R82") (pin "1") (pinfunction "1_1") (pintype "passive"))
      (node (ref "U$5") (pin "SCL") (pinfunction "SCL_SCL") (pintype "bidirectional"))
      (node (ref "U$5") (pin "SCL2") (pinfunction "SCL2_SCL2") (pintype "bidirectional"))
    )
    (net (code "99") (name "SDA") (class "Default")
      (node (ref "IC3") (pin "44") (pinfunction "(SDA/INT1)PD1_44") (pintype "bidirectional"))
      (node (ref "R6") (pin "1") (pinfunction "1_1") (pintype "passive"))
      (node (ref "U$5") (pin "SDA") (pinfunction "SDA_SDA") (pintype "bidirectional"))
      (node (ref "U$5") (pin "SDA2") (pinfunction "SDA2_SDA2") (pintype "bidirectional"))
    )
    (net (code "100") (name "TXD") (class "Default")
      (node (ref "IC3") (pin "46") (pinfunction "(TXD1/INT3)PD3_46") (pintype "bidirectional"))
      (node (ref "U$6") (pin "TXD") (pinfunction "TXD_TXD") (pintype "bidirectional"))
      (node (ref "U$6") (pin "TXD2") (pinfunction "TXD2_TXD2") (pintype "bidirectional"))
    )
    (net (code "101") (name "unconnected-(IC3-(CLKO{slash}ICP3{slash}INT7)PE7-Pad9)") (class "Default")
      (node (ref "IC3") (pin "9") (pinfunction "(CLKO/ICP3/INT7)PE7_9") (pintype "bidirectional"))
    )
    (net (code "102") (name "unconnected-(IC3-(ICP1)PD4-Pad47)") (class "Default")
      (node (ref "IC3") (pin "47") (pinfunction "(ICP1)PD4_47") (pintype "bidirectional"))
    )
    (net (code "103") (name "unconnected-(IC3-(OC0A{slash}OC1C{slash}PCINT7)PB7-Pad26)") (class "Default")
      (node (ref "IC3") (pin "26") (pinfunction "(OC0A/OC1C/PCINT7)PB7_26") (pintype "bidirectional"))
    )
    (net (code "104") (name "unconnected-(IC3-(OC0B)PG5-Pad1)") (class "Default")
      (node (ref "IC3") (pin "1") (pinfunction "(OC0B)PG5_1") (pintype "bidirectional"))
    )
    (net (code "105") (name "unconnected-(IC3-(OC1A{slash}PCINT5)PB5-Pad24)") (class "Default")
      (node (ref "IC3") (pin "24") (pinfunction "(OC1A/PCINT5)PB5_24") (pintype "bidirectional"))
    )
    (net (code "106") (name "unconnected-(IC3-(OC1B{slash}PCINT6)PB6-Pad25)") (class "Default")
      (node (ref "IC3") (pin "25") (pinfunction "(OC1B/PCINT6)PB6_25") (pintype "bidirectional"))
    )
    (net (code "107") (name "unconnected-(IC3-(OC2A{slash}PCINT4)PB4-Pad23)") (class "Default")
      (node (ref "IC3") (pin "23") (pinfunction "(OC2A/PCINT4)PB4_23") (pintype "bidirectional"))
    )
    (net (code "108") (name "unconnected-(IC3-(OC3A{slash}AIN1)PE3-Pad5)") (class "Default")
      (node (ref "IC3") (pin "5") (pinfunction "(OC3A/AIN1)PE3_5") (pintype "bidirectional"))
    )
    (net (code "109") (name "unconnected-(IC3-(OC3B{slash}INT4)PE4-Pad6)") (class "Default")
      (node (ref "IC3") (pin "6") (pinfunction "(OC3B/INT4)PE4_6") (pintype "bidirectional"))
    )
    (net (code "110") (name "unconnected-(IC3-(OC3C{slash}INT5)PE5-Pad7)") (class "Default")
      (node (ref "IC3") (pin "7") (pinfunction "(OC3C/INT5)PE5_7") (pintype "bidirectional"))
    )
    (net (code "111") (name "unconnected-(IC3-(RXD0{slash}PCIN8)PE0-Pad2)") (class "Default")
      (node (ref "IC3") (pin "2") (pinfunction "(RXD0/PCIN8)PE0_2") (pintype "bidirectional"))
    )
    (net (code "112") (name "unconnected-(IC3-(T0)PD7-Pad50)") (class "Default")
      (node (ref "IC3") (pin "50") (pinfunction "(T0)PD7_50") (pintype "bidirectional"))
    )
    (net (code "113") (name "unconnected-(IC3-(T1)PD6-Pad49)") (class "Default")
      (node (ref "IC3") (pin "49") (pinfunction "(T1)PD6_49") (pintype "bidirectional"))
    )
    (net (code "114") (name "unconnected-(IC3-(T3{slash}INT6)PE6-Pad8)") (class "Default")
      (node (ref "IC3") (pin "8") (pinfunction "(T3/INT6)PE6_8") (pintype "bidirectional"))
    )
    (net (code "115") (name "unconnected-(IC3-(TOSC1)PG4-Pad29)") (class "Default")
      (node (ref "IC3") (pin "29") (pinfunction "(TOSC1)PG4_29") (pintype "bidirectional"))
    )
    (net (code "116") (name "unconnected-(IC3-(TOSC2)PG3-Pad28)") (class "Default")
      (node (ref "IC3") (pin "28") (pinfunction "(TOSC2)PG3_28") (pintype "bidirectional"))
    )
    (net (code "117") (name "unconnected-(IC3-(TXD0)PE1-Pad3)") (class "Default")
      (node (ref "IC3") (pin "3") (pinfunction "(TXD0)PE1_3") (pintype "bidirectional"))
    )
    (net (code "118") (name "unconnected-(IC3-(XCK0{slash}AIN0)PE2-Pad4)") (class "Default")
      (node (ref "IC3") (pin "4") (pinfunction "(XCK0/AIN0)PE2_4") (pintype "bidirectional"))
    )
    (net (code "119") (name "unconnected-(IC3-(XCK1)PD5-Pad48)") (class "Default")
      (node (ref "IC3") (pin "48") (pinfunction "(XCK1)PD5_48") (pintype "bidirectional"))
    )
    (net (code "120") (name "unconnected-(IC3-PH0(RXD2)-Pad12)") (class "Default")
      (node (ref "IC3") (pin "12") (pinfunction "PH0(RXD2)_12") (pintype "bidirectional"))
    )
    (net (code "121") (name "unconnected-(IC3-PH1(TXD2)-Pad13)") (class "Default")
      (node (ref "IC3") (pin "13") (pinfunction "PH1(TXD2)_13") (pintype "bidirectional"))
    )
    (net (code "122") (name "unconnected-(IC3-PH2(XCK2)-Pad14)") (class "Default")
      (node (ref "IC3") (pin "14") (pinfunction "PH2(XCK2)_14") (pintype "bidirectional"))
    )
    (net (code "123") (name "unconnected-(IC3-PH3(OC4A)-Pad15)") (class "Default")
      (node (ref "IC3") (pin "15") (pinfunction "PH3(OC4A)_15") (pintype "bidirectional"))
    )
    (net (code "124") (name "unconnected-(IC3-PH4(OC4B)-Pad16)") (class "Default")
      (node (ref "IC3") (pin "16") (pinfunction "PH4(OC4B)_16") (pintype "bidirectional"))
    )
    (net (code "125") (name "unconnected-(IC3-PH5(OC4C)-Pad17)") (class "Default")
      (node (ref "IC3") (pin "17") (pinfunction "PH5(OC4C)_17") (pintype "bidirectional"))
    )
    (net (code "126") (name "unconnected-(IC3-PH6(OC2B)-Pad18)") (class "Default")
      (node (ref "IC3") (pin "18") (pinfunction "PH6(OC2B)_18") (pintype "bidirectional"))
    )
    (net (code "127") (name "unconnected-(IC3-PH7(T4)-Pad27)") (class "Default")
      (node (ref "IC3") (pin "27") (pinfunction "PH7(T4)_27") (pintype "bidirectional"))
    )
    (net (code "128") (name "unconnected-(IC3-PJ2(XCK3{slash}PCINT11)-Pad65)") (class "Default")
      (node (ref "IC3") (pin "65") (pinfunction "PJ2(XCK3/PCINT11)_65") (pintype "bidirectional"))
    )
    (net (code "129") (name "unconnected-(IC3-PJ3(PCINT12)-Pad66)") (class "Default")
      (node (ref "IC3") (pin "66") (pinfunction "PJ3(PCINT12)_66") (pintype "bidirectional"))
    )
    (net (code "130") (name "unconnected-(IC3-PJ4(PCINT13)-Pad67)") (class "Default")
      (node (ref "IC3") (pin "67") (pinfunction "PJ4(PCINT13)_67") (pintype "bidirectional"))
    )
    (net (code "131") (name "unconnected-(IC3-PJ5(PCINT14)-Pad68)") (class "Default")
      (node (ref "IC3") (pin "68") (pinfunction "PJ5(PCINT14)_68") (pintype "bidirectional"))
    )
    (net (code "132") (name "unconnected-(IC3-PJ6(PCINT15)-Pad69)") (class "Default")
      (node (ref "IC3") (pin "69") (pinfunction "PJ6(PCINT15)_69") (pintype "bidirectional"))
    )
    (net (code "133") (name "unconnected-(IC3-PJ7-Pad79)") (class "Default")
      (node (ref "IC3") (pin "79") (pinfunction "PJ7_79") (pintype "bidirectional"))
    )
    (net (code "134") (name "unconnected-(U$1-PadLEGO)") (class "Default")
      (node (ref "U$1") (pin "LEGO") (pinfunction "LEGO_LEGO") (pintype "bidirectional"))
    )
    (net (code "135") (name "unconnected-(U$2-PadLEGO)") (class "Default")
      (node (ref "U$2") (pin "LEGO") (pinfunction "LEGO_LEGO") (pintype "bidirectional"))
    )
    (net (code "136") (name "unconnected-(U$3-PadLEGO)") (class "Default")
      (node (ref "U$3") (pin "LEGO") (pinfunction "LEGO_LEGO") (pintype "bidirectional"))
    )
    (net (code "137") (name "unconnected-(U$4-PadLEGO)") (class "Default")
      (node (ref "U$4") (pin "LEGO") (pinfunction "LEGO_LEGO") (pintype "bidirectional"))
    )
  )
)
